# Acoustics_Board_Power.net
KiCad netlist of a schematic drawn in Altium Designer
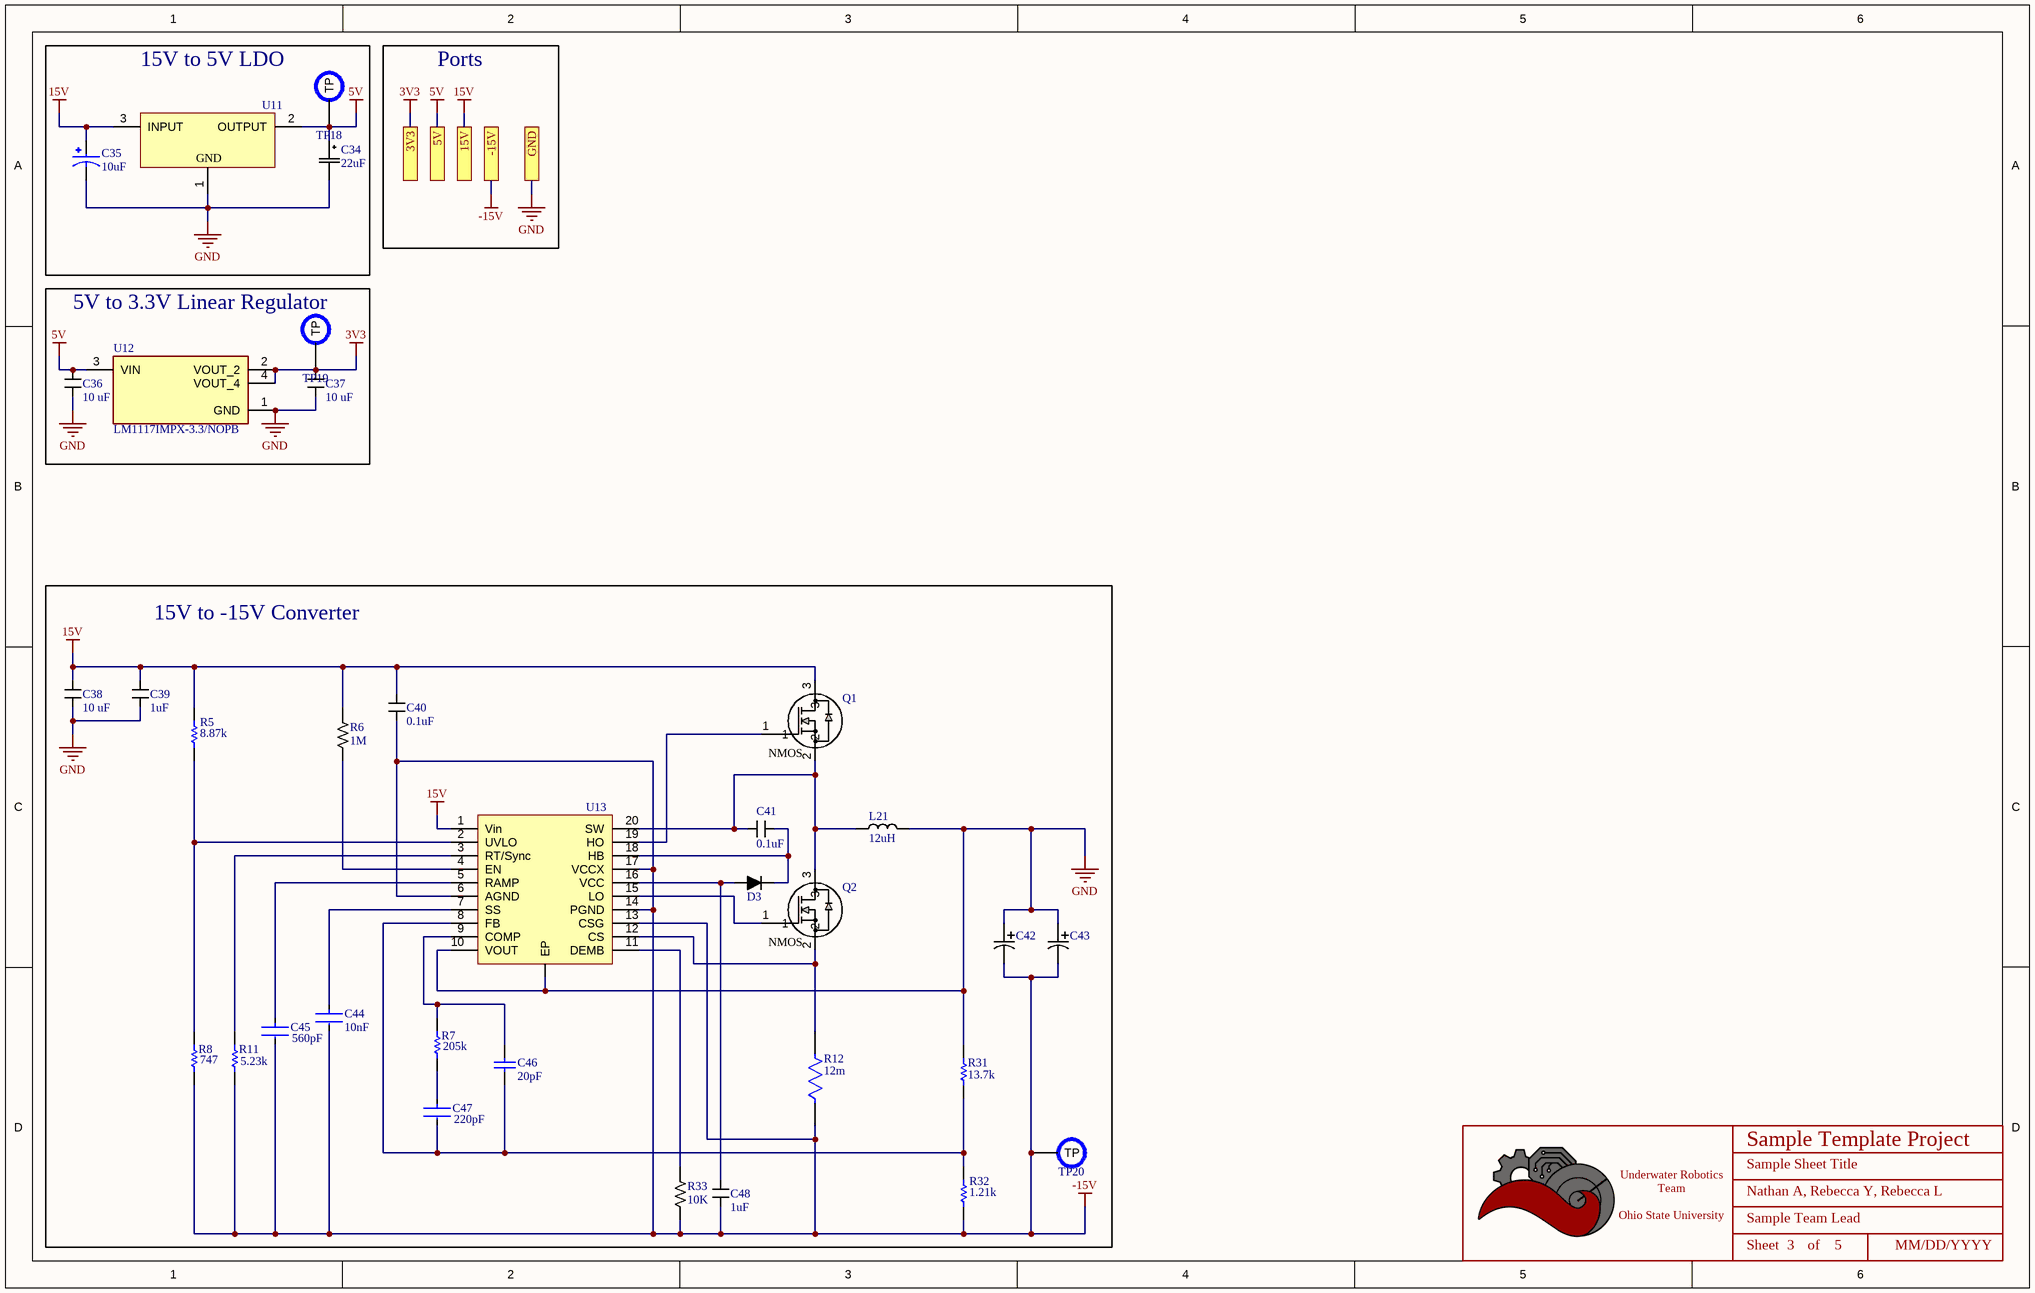
[diagram p0: Acoustics Board Power.SchDoc]

(export (version "E")
  (design (tool "Eeschema 10.0.6"))
  (components
    (comp (ref "C34")
      (value "22uF")
      (footprint "PCAP_8x5.4-ELECT_NCA")
      (description "22 µF 35 V Aluminum Electrolytic Capacitors Radial, Can - SMD 1000 Hrs")
      (fields
        (field (name "VOLTAGE") "35V")
        (field (name "Comment") "22uF electrolytic 35 V")
        (field (name "MADE BY") "Robert Pafford")
      )
      (libsource (lib "Capacitors") (part "CAP ALUM 22UF 20% 35V SMD"))
    )
    (comp (ref "C35")
      (value "10uF")
      (footprint "CAP_EEHZC1J100P")
      (description "10 µF 63 V Aluminum - Polymer Capacitors Radial, Can SMD 120mOhm")
      (fields
        (field (name "TOLERANCE") "+/- 20%")
        (field (name "Comment") "10uF electrolytic 63V")
        (field (name "MADE BY") "Robert Pafford")
      )
      (libsource (lib "Capacitors") (part "CAP ALUM 10UF 20% 63V SMD"))
    )
    (comp (ref "C36")
      (value "10uF Ceramic 6.3V")
      (footprint "CAPACITOR_0603")
      (description "Cap 10uF 6.3V +/-20%\r\nCeramic 0603")
      (fields
        (field (name "TOLERANCE") "+/- 20%")
        (field (name "VOLTAGE") "6.3V")
        (field (name "VALUE (UF)") "10 uF")
        (field (name "MADE BY") "Flip B")
      )
      (libsource (lib "Capacitors") (part "CAPACITOR_10uF_0603"))
    )
    (comp (ref "C37")
      (value "10uF Ceramic 6.3V")
      (footprint "CAPACITOR_0603")
      (description "Cap 10uF 6.3V +/-20%\r\nCeramic 0603")
      (fields
        (field (name "TOLERANCE") "+/- 20%")
        (field (name "VOLTAGE") "6.3V")
        (field (name "VALUE (UF)") "10 uF")
        (field (name "MADE BY") "Flip B")
      )
      (libsource (lib "Capacitors") (part "CAPACITOR_10uF_0603"))
    )
    (comp (ref "C38")
      (value "10uF Ceramic 6.3V")
      (footprint "CAPACITOR_0603")
      (description "Cap 10uF 6.3V +/-20%\r\nCeramic 0603")
      (fields
        (field (name "TOLERANCE") "+/- 20%")
        (field (name "VOLTAGE") "6.3V")
        (field (name "VALUE (UF)") "10 uF")
        (field (name "MADE BY") "Flip B")
      )
      (libsource (lib "Capacitors") (part "CAPACITOR_10uF_0603"))
    )
    (comp (ref "C39")
      (value "1uF")
      (footprint "CAPACITOR_0402")
      (description "Cap 1uF 16V +/-10%\r\nCeramic 0402")
      (fields
        (field (name "TOLERANCE") "+/- 10%")
        (field (name "VOLTAGE") "16V")
        (field (name "MADE BY") "Robert Pafford")
      )
      (libsource (lib "Capacitors") (part "CAPACITOR_1uF_0402"))
    )
    (comp (ref "C40")
      (value "0.1uF")
      (footprint "CAPACITOR_0402")
      (description "Cap 100nF 25V +/-10%\r\nCeramic 0402")
      (fields
        (field (name "TOLERANCE") "+/- 10%")
        (field (name "VOLTAGE") "25V")
        (field (name "MADE BY") "Robert Pafford")
      )
      (libsource (lib "Capacitors") (part "CAPACITOR_0.1uF_0402"))
    )
    (comp (ref "C41")
      (value "0.1uF")
      (footprint "CAPACITOR_0402")
      (description "Cap 100nF 25V +/-10%\r\nCeramic 0402")
      (fields
        (field (name "TOLERANCE") "+/- 10%")
        (field (name "VOLTAGE") "25V")
        (field (name "MADE BY") "Robert Pafford")
      )
      (libsource (lib "Capacitors") (part "CAPACITOR_0.1uF_0402"))
    )
    (comp (ref "C42")
      (value "EEH-ZC1E331P")
      (footprint "PCAP_EEHZ_G_PAN")
      (description "No Description Available")
      (fields (field (name "COPYRIGHT") "Copyright (C) 2024 Ultra Librarian. All rights reserved."))
      (libsource (lib "Capacitors") (part "EEH-ZC1E331P"))
    )
    (comp (ref "C43")
      (value "EEH-ZC1E331P")
      (footprint "PCAP_EEHZ_G_PAN")
      (description "No Description Available")
      (fields (field (name "COPYRIGHT") "Copyright (C) 2024 Ultra Librarian. All rights reserved."))
      (libsource (lib "Capacitors") (part "EEH-ZC1E331P"))
    )
    (comp (ref "C44")
      (value "10nF")
      (footprint "CAPACITOR_0402")
      (description "CAP CER 10000PF 50V X7R 0402")
      (fields
        (field (name "OCTOPART") "https://octopart.com/cc0402krx7r9bb103-yageo-8376513")
        (field (name "MANUFACTURER PART NUMBER") "CC0402KRX7R9BB103")
      )
      (libsource (lib "Capacitors") (part "CAP CER 0.01 UF 0402"))
    )
    (comp (ref "C45")
      (value "CL10C221JB8NNNC")
      (footprint "FP-CL10-IPC_C")
      (description "Cap Ceramic 220pF 50V C0G ±5% Pad SMD 0603 +125°C T/R")
      (fields
        (field (name "VOLTAGE") "50V")
        (field (name "CAPACITANCE") "560pF")
        (field (name "TOLERANCE") "5%")
      )
      (libsource (lib "Altium Content Vault") (part "b4654b650e69147ec39a6b967a45e02"))
    )
    (comp (ref "C46")
      (value "CL10C200JB8NNNC")
      (footprint "CAPC1608X90X30LL10T20")
      (description "Chip Capacitor, 20 pF, +/- 5%, 50 V, -55 to 85 degC, 0603 (1608 Metric), RoHS, Tape and Reel")
      (fields (field (name "MANUFACTURER") "Samsung Electro-Mechanics") (field (name "CAPACITANCE") "20pF"))
      (libsource (lib "Altium Content Vault") (part "CAP-NP-2"))
    )
    (comp (ref "C47")
      (value "CL10C221JB8NNNC")
      (footprint "FP-CL10-IPC_C")
      (description "Cap Ceramic 220pF 50V C0G ±5% Pad SMD 0603 +125°C T/R")
      (fields
        (field (name "VOLTAGE") "50V")
        (field (name "CAPACITANCE") "220pF")
        (field (name "TOLERANCE") "5%")
      )
      (libsource (lib "Altium Content Vault") (part "b4654b650e69147ec39a6b967a45e02"))
    )
    (comp (ref "C48")
      (value "1uF")
      (footprint "CAPACITOR_0402")
      (description "Cap 1uF 16V +/-10%\r\nCeramic 0402")
      (fields
        (field (name "TOLERANCE") "+/- 10%")
        (field (name "VOLTAGE") "16V")
        (field (name "MADE BY") "Robert Pafford")
      )
      (libsource (lib "Capacitors") (part "CAPACITOR_1uF_0402"))
    )
    (comp (ref "D3")
      (value "B330-13-F")
      (footprint "DO-214AB")
      (description "Schottky Diode, 30V reverse breakdown, 3A, Vf = 0.500V")
      (fields (field (name "MADE BY") "Tyson N."))
      (libsource (lib "Diodes") (part "SCHOTTKY_30V_3A"))
    )
    (comp (ref "L21")
      (value "12uH")
      (footprint "INDUCTOR_0603")
      (description "12 µH Shielded Multilayer Inductor 10 mA 1.8Ohm Max 0603 (1608 Metric)")
      (fields
        (field (name "TOLERANCE") "+/- 20%")
        (field (name "Comment") "FIXED IND 12UH 10MA 1.8 OHM SMD")
        (field (name "MADE BY") "Robert Pafford")
      )
      (libsource (lib "Inductors") (part "INDUCTOR_12uH_0603"))
    )
    (comp (ref "Q1")
      (value "MOSFET N-Ch 80V 100A D2PAK")
      (footprint "D2PAK")
      (description "N-Channel 80V 100A (Ta) 306W (Ta), Surface Mount D2PAK")
      (fields
        (field (name "MANUFACTURER _PART_NUMBER") "PSMN4R4-80BS,118")
        (field (name "CREATED BY") "Flip B")
      )
      (libsource (lib "Transistors") (part "PSMN4R4-80BS,118"))
    )
    (comp (ref "Q2")
      (value "MOSFET N-Ch 80V 100A D2PAK")
      (footprint "D2PAK")
      (description "N-Channel 80V 100A (Ta) 306W (Ta), Surface Mount D2PAK")
      (fields
        (field (name "MANUFACTURER _PART_NUMBER") "PSMN4R4-80BS,118")
        (field (name "CREATED BY") "Flip B")
      )
      (libsource (lib "Transistors") (part "PSMN4R4-80BS,118"))
    )
    (comp (ref "R5")
      (value "RC0603FR-078K87L")
      (footprint "RESC1608X55X25LL10T15")
      (fields
        (field (name "MANUFACTURER") "Yageo")
        (field (name "PART NUMBER") "RC0603FR-071K21L")
        (field (name "RESISTANCE") "8.87k")
      )
      (libsource (lib "Altium Content Vault") (part "RES"))
    )
    (comp (ref "R6")
      (value "1M Ohm 1% 1/16W")
      (footprint "RESISTOR_0402")
      (description "RES 1M OHM 1% 1/16W 0402")
      (fields
        (field (name "TOLERANCE") "+/- 1%")
        (field (name "VALUE  (OHMS)") "1M")
        (field (name "MADE BY") "Robert Pafford")
      )
      (libsource (lib "Resistors") (part "RESISTOR_1M_0402"))
    )
    (comp (ref "R7")
      (value "RC0402FR-07205KL")
      (footprint "RESC1005X40X25ML05T10")
      (fields (field (name "MANUFACTURER") "Yageo / Phycomp") (field (name "RESISTANCE") "205k"))
      (libsource (lib "Altium Content Vault") (part "RES"))
    )
    (comp (ref "R8")
      (value "CRCW0603787RFKEA")
      (footprint "RESC1609X50X30NL10T20")
      (fields (field (name "MANUFACTURER") "Vishay Dale") (field (name "RESISTANCE") "747"))
      (libsource (lib "Altium Content Vault") (part "RES"))
    )
    (comp (ref "R11")
      (value "RC0402FR-075K23L")
      (footprint "RESC1005X40X25NL05T10")
      (fields (field (name "MANUFACTURER") "Yageo") (field (name "RESISTANCE") "5.23k"))
      (libsource (lib "Altium Content Vault") (part "RES"))
    )
    (comp (ref "R12")
      (value "CSR1206FK12L0")
      (footprint "FP-CSR1206-IPC_B")
      (description "General Purpose Thick Film Chip Resistor, 1206, 12mΩ, 1%, 0.5W")
      (fields (field (name "TOLERANCE") "1%") (field (name "RESISTANCE") "12m"))
      (libsource (lib "Altium Content Vault") (part "1029c3af85768c4190bb7ad29bc67b5"))
    )
    (comp (ref "R31")
      (value "CRCW060313K7FKEA")
      (footprint "RESC1609X50X30ML10T20")
      (fields (field (name "MANUFACTURER") "Vishay Dale") (field (name "RESISTANCE") "13.7k"))
      (libsource (lib "Altium Content Vault") (part "RES"))
    )
    (comp (ref "R32")
      (value "RC0603FR-071K21L")
      (footprint "RESC1608X55X25LL10T15")
      (fields (field (name "MANUFACTURER") "Yageo") (field (name "RESISTANCE") "1.21k"))
      (libsource (lib "Altium Content Vault") (part "RES"))
    )
    (comp (ref "R33")
      (value "10k Ohm 0.5% 1/10W")
      (footprint "RESISTOR_0603")
      (description "RES 10k OHM 0.5% 1/10W 0603")
      (fields
        (field (name "TOLERANCE") "+/- 0.5%")
        (field (name "VALUE  (OHMS)") "10K")
        (field (name "MADE BY") "Robert Pafford")
      )
      (libsource (lib "Resistors") (part "RESISTOR_10K_0.5%_0603"))
    )
    (comp (ref "TP18")
      (value "PCB Test Point")
      (footprint "TESTPOINT_1.2MM")
      (fields (field (name "MADE BY") "Robert Pafford"))
      (libsource (lib "Connectors") (part "TESTPOINT"))
    )
    (comp (ref "TP19")
      (value "PCB Test Point")
      (footprint "TESTPOINT_1.2MM")
      (fields (field (name "MADE BY") "Robert Pafford"))
      (libsource (lib "Connectors") (part "TESTPOINT"))
    )
    (comp (ref "TP20")
      (value "PCB Test Point")
      (footprint "TESTPOINT_1.2MM")
      (fields (field (name "MADE BY") "Robert Pafford"))
      (libsource (lib "Connectors") (part "TESTPOINT"))
    )
    (comp (ref "U11")
      (value "AZ1117IH-5.0TRG1")
      (footprint "SOT223-3")
      (description "Linear Voltage Regulator IC Positive Fixed 1 Output 1A SOT-223-3")
      (libsource (lib "Integrated Circuits") (part "AZ1117IH-5.0TRG1"))
    )
    (comp (ref "U12")
      (value "LM1117IMPX-3.3/NOPB")
      (footprint "SOT-223-4")
      (description "800-mA 15-V linear voltage regulator 4-SOT-223 -40 to 125")
      (fields (field (name "MF") "Texas Instruments"))
      (libsource (lib "Integrated Circuits") (part "LM1117IMPX-3.3/NOPB"))
    )
    (comp (ref "U13")
      (value "LM25116")
      (footprint "LM25116")
      (description "IC REG CTRLR BUCK 20TSSOP")
      (libsource (lib "Integrated Circuits") (part "LM25116"))
    )
  )
  (nets
    (net (code "1") (name "-15V") (class "Default")
      (node (ref "C40") (pin "2") (pinfunction "2_2") (pintype "passive"))
      (node (ref "C42") (pin "2") (pinfunction "2_2") (pintype "passive"))
      (node (ref "C43") (pin "2") (pinfunction "2_2") (pintype "passive"))
      (node (ref "C44") (pin "2") (pinfunction "2_2") (pintype "passive"))
      (node (ref "C45") (pin "2") (pinfunction "2_2") (pintype "passive"))
      (node (ref "C48") (pin "2") (pinfunction "2_2") (pintype "passive"))
      (node (ref "R11") (pin "1") (pinfunction "1_1") (pintype "passive"))
      (node (ref "R12") (pin "1") (pinfunction "1_1") (pintype "passive"))
      (node (ref "R32") (pin "2") (pinfunction "2_2") (pintype "passive"))
      (node (ref "R33") (pin "2") (pinfunction "2_2") (pintype "passive"))
      (node (ref "R8") (pin "1") (pinfunction "1_1") (pintype "passive"))
      (node (ref "TP20") (pin "TP") (pinfunction "TP_TP") (pintype "passive"))
      (node (ref "U13") (pin "13") (pinfunction "CSG_13") (pintype "passive"))
      (node (ref "U13") (pin "14") (pinfunction "PGND_14") (pintype "passive"))
      (node (ref "U13") (pin "17") (pinfunction "VCCX_17") (pintype "passive"))
      (node (ref "U13") (pin "6") (pinfunction "AGND_6") (pintype "passive"))
    )
    (net (code "2") (name "3V3") (class "Default")
      (node (ref "C37") (pin "1") (pinfunction "1_1") (pintype "passive"))
      (node (ref "TP19") (pin "TP") (pinfunction "TP_TP") (pintype "passive"))
      (node (ref "U12") (pin "2") (pinfunction "VOUT_2_2") (pintype "power_in"))
      (node (ref "U12") (pin "4") (pinfunction "VOUT_4_4") (pintype "power_in"))
    )
    (net (code "3") (name "5V") (class "Default")
      (node (ref "C34") (pin "1") (pinfunction "1_1") (pintype "passive"))
      (node (ref "C36") (pin "1") (pinfunction "1_1") (pintype "passive"))
      (node (ref "TP18") (pin "TP") (pinfunction "TP_TP") (pintype "passive"))
      (node (ref "U11") (pin "2") (pinfunction "OUTPUT_2") (pintype "passive"))
      (node (ref "U12") (pin "3") (pinfunction "VIN_3") (pintype "power_in"))
    )
    (net (code "4") (name "15V") (class "Default")
      (node (ref "C35") (pin "1") (pinfunction "1_1") (pintype "passive"))
      (node (ref "C38") (pin "1") (pinfunction "1_1") (pintype "passive"))
      (node (ref "C39") (pin "1") (pinfunction "1_1") (pintype "passive"))
      (node (ref "C40") (pin "1") (pinfunction "1_1") (pintype "passive"))
      (node (ref "Q1") (pin "3") (pinfunction "3_3") (pintype "passive"))
      (node (ref "R5") (pin "1") (pinfunction "1_1") (pintype "passive"))
      (node (ref "R6") (pin "1") (pinfunction "1_1") (pintype "passive"))
      (node (ref "U11") (pin "3") (pinfunction "INPUT_3") (pintype "passive"))
      (node (ref "U13") (pin "1") (pinfunction "Vin_1") (pintype "passive"))
    )
    (net (code "5") (name "GND") (class "Default")
      (node (ref "C34") (pin "2") (pinfunction "2_2") (pintype "passive"))
      (node (ref "C35") (pin "2") (pinfunction "2_2") (pintype "passive"))
      (node (ref "C36") (pin "2") (pinfunction "2_2") (pintype "passive"))
      (node (ref "C37") (pin "2") (pinfunction "2_2") (pintype "passive"))
      (node (ref "C38") (pin "2") (pinfunction "2_2") (pintype "passive"))
      (node (ref "C39") (pin "2") (pinfunction "2_2") (pintype "passive"))
      (node (ref "C42") (pin "1") (pinfunction "1_1") (pintype "passive"))
      (node (ref "C43") (pin "1") (pinfunction "1_1") (pintype "passive"))
      (node (ref "L21") (pin "1") (pinfunction "1_1") (pintype "passive"))
      (node (ref "R31") (pin "2") (pinfunction "2_2") (pintype "passive"))
      (node (ref "U11") (pin "1") (pinfunction "GND_1") (pintype "passive"))
      (node (ref "U12") (pin "1") (pinfunction "GND_1") (pintype "power_in"))
      (node (ref "U13") (pin "10") (pinfunction "VOUT_10") (pintype "passive"))
      (node (ref "U13") (pin "21") (pinfunction "EP_21") (pintype "passive"))
    )
    (net (code "6") (name "Net-(C47-Pad1)") (class "Default")
      (node (ref "C47") (pin "1") (pinfunction "1_1") (pintype "passive"))
      (node (ref "R7") (pin "1") (pinfunction "1_1") (pintype "passive"))
    )
    (net (code "7") (name "Net-(U13-COMP)") (class "Default")
      (node (ref "C46") (pin "1") (pinfunction "1_1") (pintype "passive"))
      (node (ref "R7") (pin "2") (pinfunction "2_2") (pintype "passive"))
      (node (ref "U13") (pin "9") (pinfunction "COMP_9") (pintype "passive"))
    )
    (net (code "8") (name "Net-(U13-CS)") (class "Default")
      (node (ref "Q2") (pin "2") (pinfunction "2_2") (pintype "passive"))
      (node (ref "R12") (pin "2") (pinfunction "2_2") (pintype "passive"))
      (node (ref "U13") (pin "12") (pinfunction "CS_12") (pintype "passive"))
    )
    (net (code "9") (name "Net-(U13-DEMB)") (class "Default")
      (node (ref "R33") (pin "1") (pinfunction "1_1") (pintype "passive"))
      (node (ref "U13") (pin "11") (pinfunction "DEMB_11") (pintype "passive"))
    )
    (net (code "10") (name "Net-(U13-EN)") (class "Default")
      (node (ref "R6") (pin "2") (pinfunction "2_2") (pintype "passive"))
      (node (ref "U13") (pin "4") (pinfunction "EN_4") (pintype "passive"))
    )
    (net (code "11") (name "Net-(U13-FB)") (class "Default")
      (node (ref "C46") (pin "2") (pinfunction "2_2") (pintype "passive"))
      (node (ref "C47") (pin "2") (pinfunction "2_2") (pintype "passive"))
      (node (ref "R31") (pin "1") (pinfunction "1_1") (pintype "passive"))
      (node (ref "R32") (pin "1") (pinfunction "1_1") (pintype "passive"))
      (node (ref "U13") (pin "8") (pinfunction "FB_8") (pintype "passive"))
    )
    (net (code "12") (name "Net-(U13-HB)") (class "Default")
      (node (ref "C41") (pin "2") (pinfunction "2_2") (pintype "passive"))
      (node (ref "D3") (pin "2") (pinfunction "2_2") (pintype "passive"))
      (node (ref "U13") (pin "18") (pinfunction "HB_18") (pintype "passive"))
    )
    (net (code "13") (name "Net-(U13-HO)") (class "Default")
      (node (ref "Q1") (pin "1") (pinfunction "1_1") (pintype "passive"))
      (node (ref "U13") (pin "19") (pinfunction "HO_19") (pintype "passive"))
    )
    (net (code "14") (name "Net-(U13-LO)") (class "Default")
      (node (ref "Q2") (pin "1") (pinfunction "1_1") (pintype "passive"))
      (node (ref "U13") (pin "15") (pinfunction "LO_15") (pintype "passive"))
    )
    (net (code "15") (name "Net-(U13-RAMP)") (class "Default")
      (node (ref "C45") (pin "1") (pinfunction "1_1") (pintype "passive"))
      (node (ref "U13") (pin "5") (pinfunction "RAMP_5") (pintype "passive"))
    )
    (net (code "16") (name "Net-(U13-RT{slash}Sync)") (class "Default")
      (node (ref "R11") (pin "2") (pinfunction "2_2") (pintype "passive"))
      (node (ref "U13") (pin "3") (pinfunction "RT/Sync_3") (pintype "passive"))
    )
    (net (code "17") (name "Net-(U13-SS)") (class "Default")
      (node (ref "C44") (pin "1") (pinfunction "1_1") (pintype "passive"))
      (node (ref "U13") (pin "7") (pinfunction "SS_7") (pintype "passive"))
    )
    (net (code "18") (name "Net-(U13-SW)") (class "Default")
      (node (ref "C41") (pin "1") (pinfunction "1_1") (pintype "passive"))
      (node (ref "L21") (pin "2") (pinfunction "2_2") (pintype "passive"))
      (node (ref "Q1") (pin "2") (pinfunction "2_2") (pintype "passive"))
      (node (ref "Q2") (pin "3") (pinfunction "3_3") (pintype "passive"))
      (node (ref "U13") (pin "20") (pinfunction "SW_20") (pintype "passive"))
    )
    (net (code "19") (name "Net-(U13-UVLO)") (class "Default")
      (node (ref "R5") (pin "2") (pinfunction "2_2") (pintype "passive"))
      (node (ref "R8") (pin "2") (pinfunction "2_2") (pintype "passive"))
      (node (ref "U13") (pin "2") (pinfunction "UVLO_2") (pintype "passive"))
    )
    (net (code "20") (name "Net-(U13-VCC)") (class "Default")
      (node (ref "C48") (pin "1") (pinfunction "1_1") (pintype "passive"))
      (node (ref "D3") (pin "1") (pinfunction "1_1") (pintype "passive"))
      (node (ref "U13") (pin "16") (pinfunction "VCC_16") (pintype "passive"))
    )
  )
)
